# Rubik_s_cube_lamp_plate.net
KiCad netlist of a schematic drawn in Altium Designer
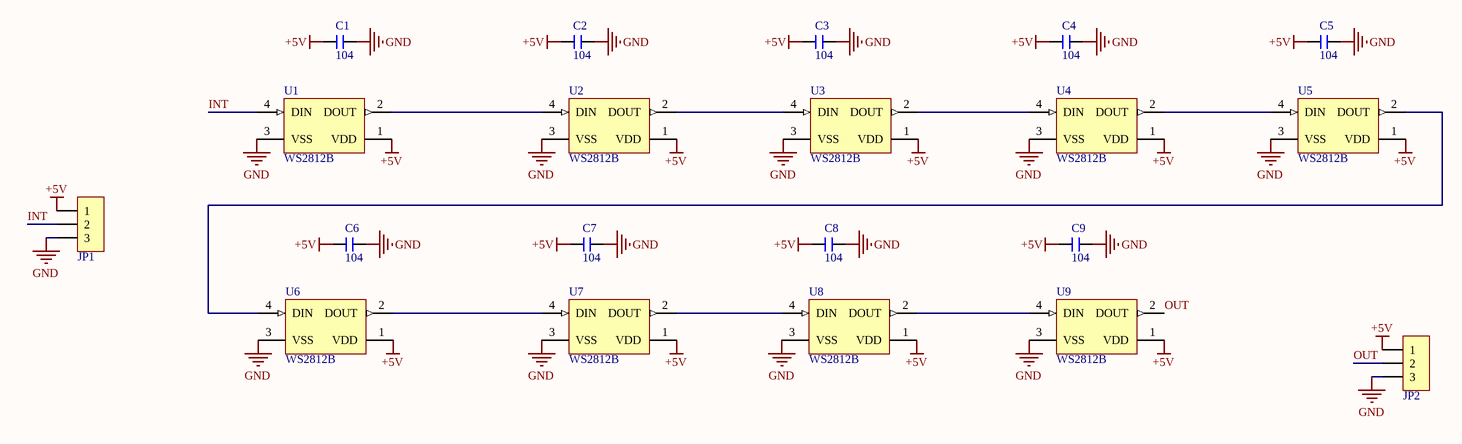
[diagram p0: Rubik's_cube_lamp_plate.SchDoc]

(export (version "E")
  (design (tool "Eeschema 10.0.6"))
  (components
    (comp (ref "C1")
      (value "104")
      (footprint "C 0603")
      (description "无极性贴片电容")
      (fields (field (name "版权归属") "源创客"))
      (libsource (lib "电阻-电容-电感") (part "C"))
    )
    (comp (ref "C2")
      (value "104")
      (footprint "C 0603")
      (description "无极性贴片电容")
      (fields (field (name "版权归属") "源创客"))
      (libsource (lib "电阻-电容-电感") (part "C"))
    )
    (comp (ref "C3")
      (value "104")
      (footprint "C 0603")
      (description "无极性贴片电容")
      (fields (field (name "版权归属") "源创客"))
      (libsource (lib "电阻-电容-电感") (part "C"))
    )
    (comp (ref "C4")
      (value "104")
      (footprint "C 0603")
      (description "无极性贴片电容")
      (fields (field (name "版权归属") "源创客"))
      (libsource (lib "电阻-电容-电感") (part "C"))
    )
    (comp (ref "C5")
      (value "104")
      (footprint "C 0603")
      (description "无极性贴片电容")
      (fields (field (name "版权归属") "源创客"))
      (libsource (lib "电阻-电容-电感") (part "C"))
    )
    (comp (ref "C6")
      (value "104")
      (footprint "C 0603")
      (description "无极性贴片电容")
      (fields (field (name "版权归属") "源创客"))
      (libsource (lib "电阻-电容-电感") (part "C"))
    )
    (comp (ref "C7")
      (value "104")
      (footprint "C 0603")
      (description "无极性贴片电容")
      (fields (field (name "版权归属") "源创客"))
      (libsource (lib "电阻-电容-电感") (part "C"))
    )
    (comp (ref "C8")
      (value "104")
      (footprint "C 0603")
      (description "无极性贴片电容")
      (fields (field (name "版权归属") "源创客"))
      (libsource (lib "电阻-电容-电感") (part "C"))
    )
    (comp (ref "C9")
      (value "104")
      (footprint "C 0603")
      (description "无极性贴片电容")
      (fields (field (name "版权归属") "源创客"))
      (libsource (lib "电阻-电容-电感") (part "C"))
    )
    (comp (ref "JP1")
      (value "HDR-1X3")
      (footprint "XH2.54-3P")
      (description "3P接插件")
      (fields (field (name "版权归属") "源创客"))
      (libsource (lib "接插件") (part "Header 3"))
    )
    (comp (ref "JP2")
      (value "HDR-1X3")
      (footprint "XH2.54-3P")
      (description "3P接插件")
      (fields (field (name "版权归属") "源创客"))
      (libsource (lib "接插件") (part "Header 3"))
    )
    (comp (ref "U1")
      (value "WS2812B")
      (footprint "ADAI-WS2812B_V")
      (fields (field (name "MANUFACTURER") "Adafruit Industries"))
      (libsource (lib "视能宝") (part "ADAI-WS2812B-4"))
    )
    (comp (ref "U2")
      (value "WS2812B")
      (footprint "ADAI-WS2812B_V")
      (fields (field (name "MANUFACTURER") "Adafruit Industries"))
      (libsource (lib "视能宝") (part "ADAI-WS2812B-4"))
    )
    (comp (ref "U3")
      (value "WS2812B")
      (footprint "ADAI-WS2812B_V")
      (fields (field (name "MANUFACTURER") "Adafruit Industries"))
      (libsource (lib "视能宝") (part "ADAI-WS2812B-4"))
    )
    (comp (ref "U4")
      (value "WS2812B")
      (footprint "ADAI-WS2812B_V")
      (fields (field (name "MANUFACTURER") "Adafruit Industries"))
      (libsource (lib "视能宝") (part "ADAI-WS2812B-4"))
    )
    (comp (ref "U5")
      (value "WS2812B")
      (footprint "ADAI-WS2812B_V")
      (fields (field (name "MANUFACTURER") "Adafruit Industries"))
      (libsource (lib "视能宝") (part "ADAI-WS2812B-4"))
    )
    (comp (ref "U6")
      (value "WS2812B")
      (footprint "ADAI-WS2812B_V")
      (fields (field (name "MANUFACTURER") "Adafruit Industries"))
      (libsource (lib "视能宝") (part "ADAI-WS2812B-4"))
    )
    (comp (ref "U7")
      (value "WS2812B")
      (footprint "ADAI-WS2812B_V")
      (fields (field (name "MANUFACTURER") "Adafruit Industries"))
      (libsource (lib "视能宝") (part "ADAI-WS2812B-4"))
    )
    (comp (ref "U8")
      (value "WS2812B")
      (footprint "ADAI-WS2812B_V")
      (fields (field (name "MANUFACTURER") "Adafruit Industries"))
      (libsource (lib "视能宝") (part "ADAI-WS2812B-4"))
    )
    (comp (ref "U9")
      (value "WS2812B")
      (footprint "ADAI-WS2812B_V")
      (fields (field (name "MANUFACTURER") "Adafruit Industries"))
      (libsource (lib "视能宝") (part "ADAI-WS2812B-4"))
    )
  )
  (nets
    (net (code "1") (name "+5V") (class "Default")
      (node (ref "C1") (pin "2") (pinfunction "2_2") (pintype "passive"))
      (node (ref "C2") (pin "2") (pinfunction "2_2") (pintype "passive"))
      (node (ref "C3") (pin "2") (pinfunction "2_2") (pintype "passive"))
      (node (ref "C4") (pin "2") (pinfunction "2_2") (pintype "passive"))
      (node (ref "C5") (pin "2") (pinfunction "2_2") (pintype "passive"))
      (node (ref "C6") (pin "2") (pinfunction "2_2") (pintype "passive"))
      (node (ref "C7") (pin "2") (pinfunction "2_2") (pintype "passive"))
      (node (ref "C8") (pin "2") (pinfunction "2_2") (pintype "passive"))
      (node (ref "C9") (pin "2") (pinfunction "2_2") (pintype "passive"))
      (node (ref "JP1") (pin "1") (pinfunction "1_1") (pintype "passive"))
      (node (ref "JP2") (pin "1") (pinfunction "1_1") (pintype "passive"))
      (node (ref "U1") (pin "1") (pinfunction "VDD_1") (pintype "power_in"))
      (node (ref "U2") (pin "1") (pinfunction "VDD_1") (pintype "power_in"))
      (node (ref "U3") (pin "1") (pinfunction "VDD_1") (pintype "power_in"))
      (node (ref "U4") (pin "1") (pinfunction "VDD_1") (pintype "power_in"))
      (node (ref "U5") (pin "1") (pinfunction "VDD_1") (pintype "power_in"))
      (node (ref "U6") (pin "1") (pinfunction "VDD_1") (pintype "power_in"))
      (node (ref "U7") (pin "1") (pinfunction "VDD_1") (pintype "power_in"))
      (node (ref "U8") (pin "1") (pinfunction "VDD_1") (pintype "power_in"))
      (node (ref "U9") (pin "1") (pinfunction "VDD_1") (pintype "power_in"))
    )
    (net (code "2") (name "/INT") (class "Default")
      (node (ref "JP1") (pin "2") (pinfunction "2_2") (pintype "passive"))
      (node (ref "U1") (pin "4") (pinfunction "DIN_4") (pintype "input"))
    )
    (net (code "3") (name "/OUT") (class "Default")
      (node (ref "JP2") (pin "2") (pinfunction "2_2") (pintype "passive"))
      (node (ref "U9") (pin "2") (pinfunction "DOUT_2") (pintype "output"))
    )
    (net (code "4") (name "GND") (class "Default")
      (node (ref "C1") (pin "1") (pinfunction "1_1") (pintype "passive"))
      (node (ref "C2") (pin "1") (pinfunction "1_1") (pintype "passive"))
      (node (ref "C3") (pin "1") (pinfunction "1_1") (pintype "passive"))
      (node (ref "C4") (pin "1") (pinfunction "1_1") (pintype "passive"))
      (node (ref "C5") (pin "1") (pinfunction "1_1") (pintype "passive"))
      (node (ref "C6") (pin "1") (pinfunction "1_1") (pintype "passive"))
      (node (ref "C7") (pin "1") (pinfunction "1_1") (pintype "passive"))
      (node (ref "C8") (pin "1") (pinfunction "1_1") (pintype "passive"))
      (node (ref "C9") (pin "1") (pinfunction "1_1") (pintype "passive"))
      (node (ref "JP1") (pin "3") (pinfunction "3_3") (pintype "passive"))
      (node (ref "JP2") (pin "3") (pinfunction "3_3") (pintype "passive"))
      (node (ref "U1") (pin "3") (pinfunction "VSS_3") (pintype "power_in"))
      (node (ref "U2") (pin "3") (pinfunction "VSS_3") (pintype "power_in"))
      (node (ref "U3") (pin "3") (pinfunction "VSS_3") (pintype "power_in"))
      (node (ref "U4") (pin "3") (pinfunction "VSS_3") (pintype "power_in"))
      (node (ref "U5") (pin "3") (pinfunction "VSS_3") (pintype "power_in"))
      (node (ref "U6") (pin "3") (pinfunction "VSS_3") (pintype "power_in"))
      (node (ref "U7") (pin "3") (pinfunction "VSS_3") (pintype "power_in"))
      (node (ref "U8") (pin "3") (pinfunction "VSS_3") (pintype "power_in"))
      (node (ref "U9") (pin "3") (pinfunction "VSS_3") (pintype "power_in"))
    )
    (net (code "5") (name "Net-(U1-DOUT)") (class "Default")
      (node (ref "U1") (pin "2") (pinfunction "DOUT_2") (pintype "output"))
      (node (ref "U2") (pin "4") (pinfunction "DIN_4") (pintype "input"))
    )
    (net (code "6") (name "Net-(U2-DOUT)") (class "Default")
      (node (ref "U2") (pin "2") (pinfunction "DOUT_2") (pintype "output"))
      (node (ref "U3") (pin "4") (pinfunction "DIN_4") (pintype "input"))
    )
    (net (code "7") (name "Net-(U3-DOUT)") (class "Default")
      (node (ref "U3") (pin "2") (pinfunction "DOUT_2") (pintype "output"))
      (node (ref "U4") (pin "4") (pinfunction "DIN_4") (pintype "input"))
    )
    (net (code "8") (name "Net-(U4-DOUT)") (class "Default")
      (node (ref "U4") (pin "2") (pinfunction "DOUT_2") (pintype "output"))
      (node (ref "U5") (pin "4") (pinfunction "DIN_4") (pintype "input"))
    )
    (net (code "9") (name "Net-(U5-DOUT)") (class "Default")
      (node (ref "U5") (pin "2") (pinfunction "DOUT_2") (pintype "output"))
      (node (ref "U6") (pin "4") (pinfunction "DIN_4") (pintype "input"))
    )
    (net (code "10") (name "Net-(U6-DOUT)") (class "Default")
      (node (ref "U6") (pin "2") (pinfunction "DOUT_2") (pintype "output"))
      (node (ref "U7") (pin "4") (pinfunction "DIN_4") (pintype "input"))
    )
    (net (code "11") (name "Net-(U7-DOUT)") (class "Default")
      (node (ref "U7") (pin "2") (pinfunction "DOUT_2") (pintype "output"))
      (node (ref "U8") (pin "4") (pinfunction "DIN_4") (pintype "input"))
    )
    (net (code "12") (name "Net-(U8-DOUT)") (class "Default")
      (node (ref "U8") (pin "2") (pinfunction "DOUT_2") (pintype "output"))
      (node (ref "U9") (pin "4") (pinfunction "DIN_4") (pintype "input"))
    )
  )
)
